# Rear_right_lamp_v3.net
KiCad netlist of a schematic drawn in EAGLE
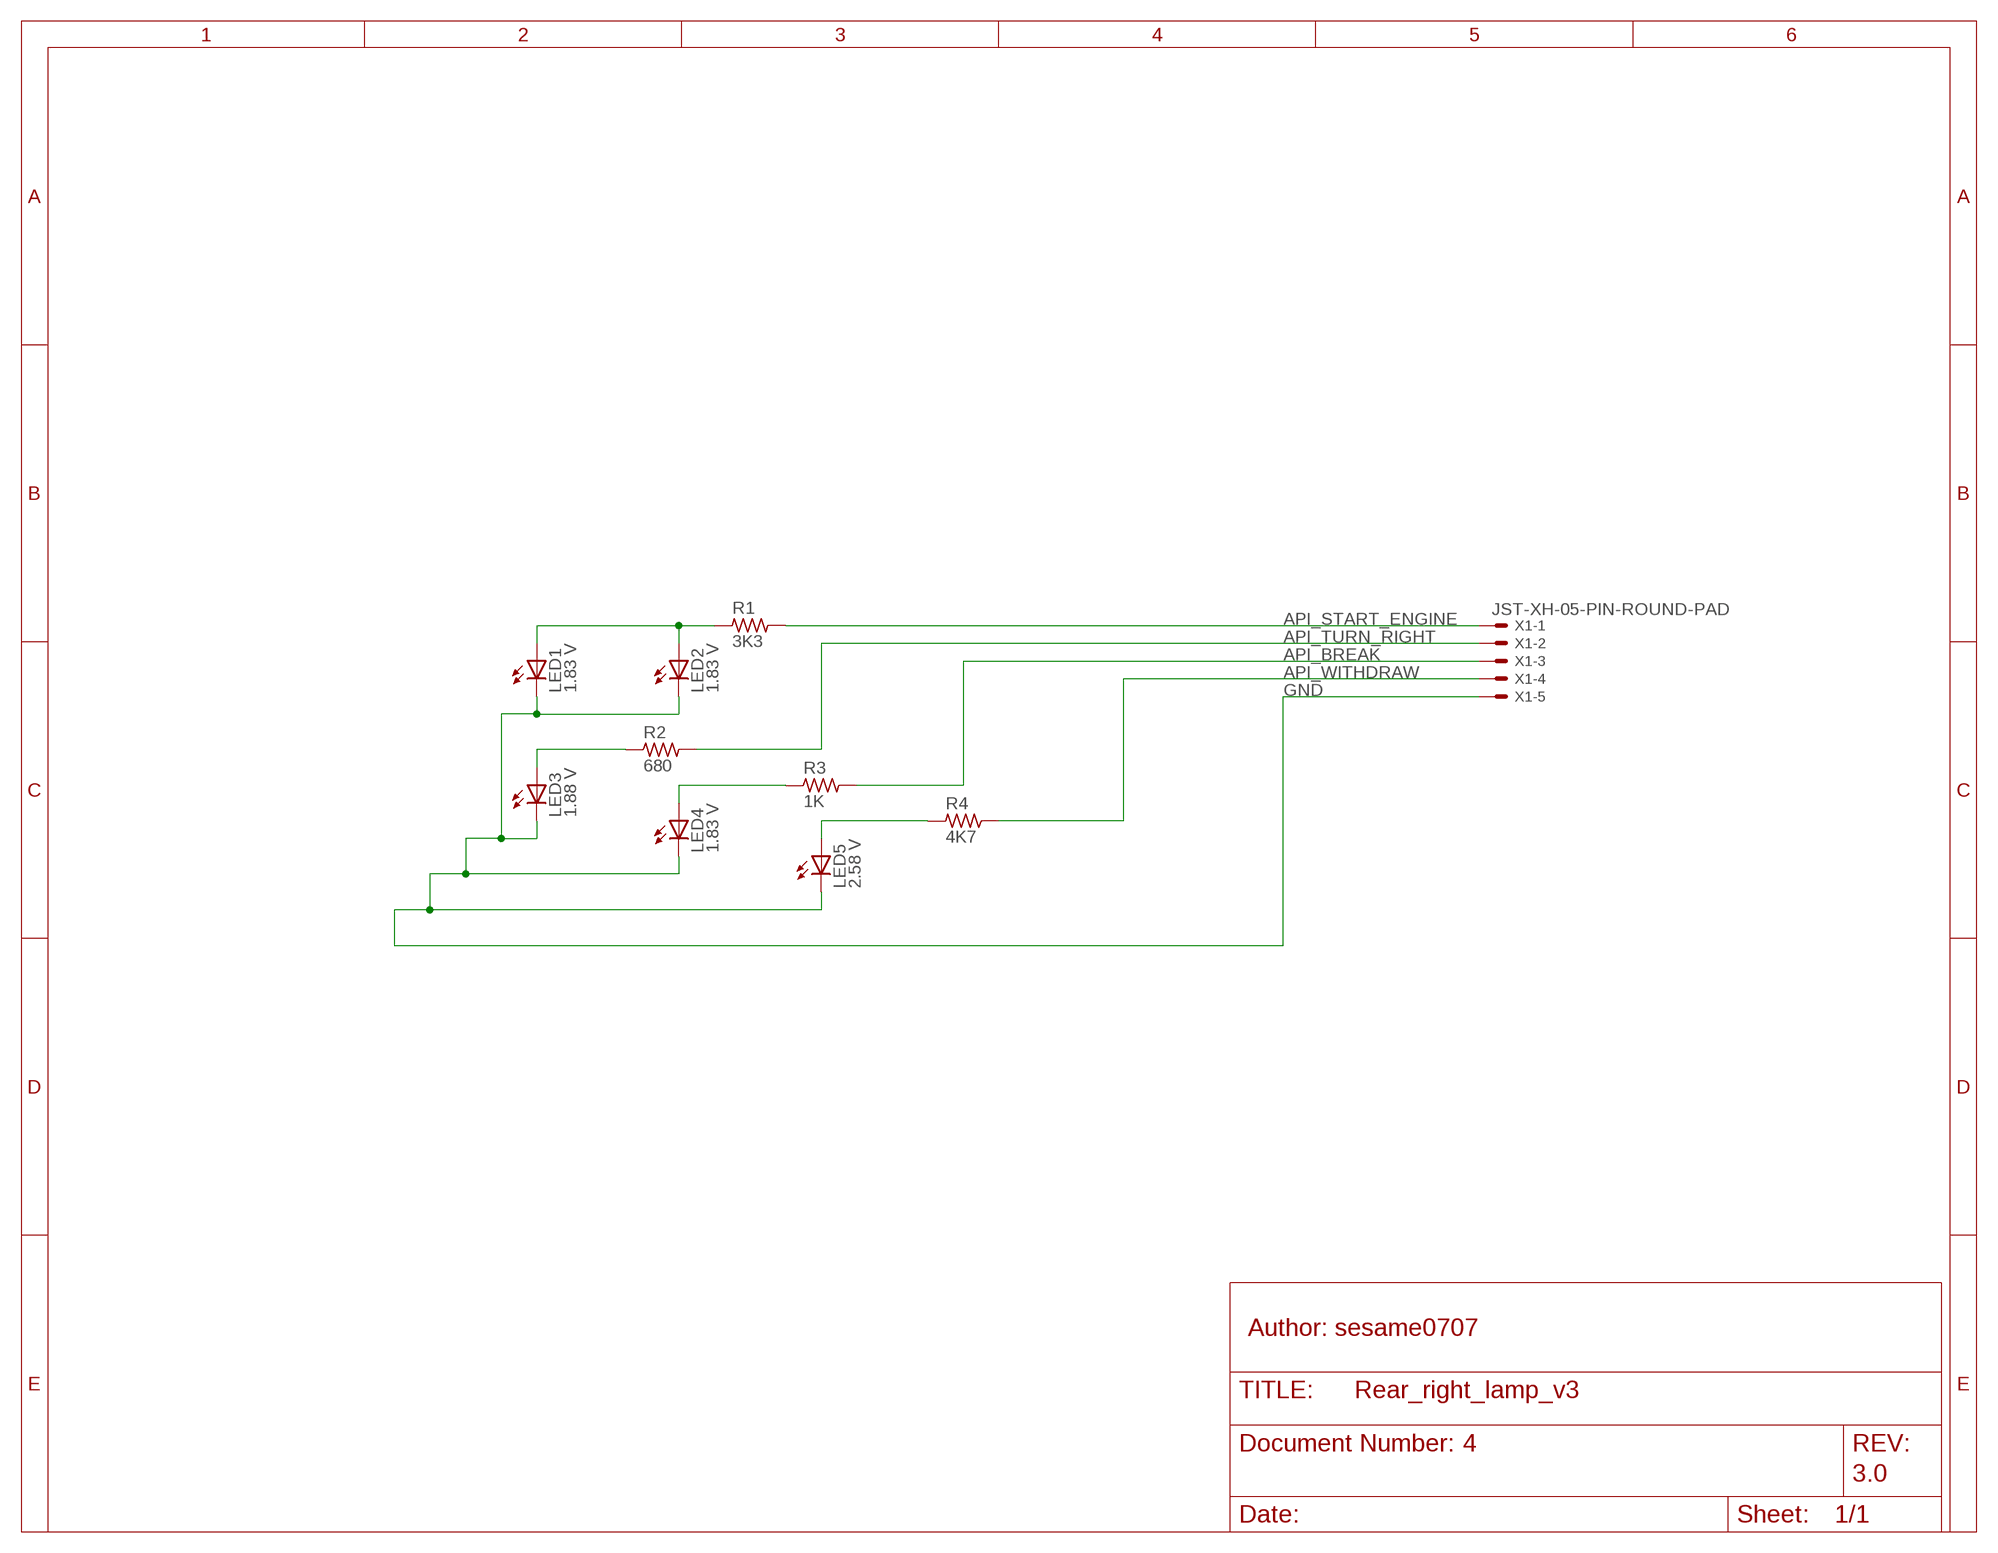
[diagram p0: schematic, sheet 1]

(export (version "E")
  (design (tool "Eeschema 10.0.6"))
  (components
    (comp (ref "LED1")
      (value "1.83 V")
      (footprint "eagle-import:LED5MM")
      (libsource (lib "eagle-import") (part "LED5MM"))
    )
    (comp (ref "LED2")
      (value "1.83 V")
      (footprint "eagle-import:LED5MM")
      (libsource (lib "eagle-import") (part "LED5MM"))
    )
    (comp (ref "LED3")
      (value "1.88 V")
      (footprint "eagle-import:LED5MM")
      (libsource (lib "eagle-import") (part "LED5MM"))
    )
    (comp (ref "LED4")
      (value "1.83 V")
      (footprint "eagle-import:LED5MM")
      (libsource (lib "eagle-import") (part "LED5MM"))
    )
    (comp (ref "LED5")
      (value "2.58 V")
      (footprint "eagle-import:LED5MM")
      (libsource (lib "eagle-import") (part "LED5MM"))
    )
    (comp (ref "R1")
      (value "3K3")
      (footprint "eagle-import:R1206")
      (libsource (lib "eagle-import") (part "R_1206"))
    )
    (comp (ref "R2")
      (value "680")
      (footprint "eagle-import:R1206")
      (libsource (lib "eagle-import") (part "R_1206"))
    )
    (comp (ref "R3")
      (value "1K")
      (footprint "eagle-import:R1206")
      (libsource (lib "eagle-import") (part "R_1206"))
    )
    (comp (ref "R4")
      (value "4K7")
      (footprint "eagle-import:R1206")
      (libsource (lib "eagle-import") (part "R_1206"))
    )
    (comp (ref "X1")
      (value "JST-XH-05-PIN-ROUND-PAD")
      (footprint "eagle-import:JST-XH-05-PACKAGE-ROUND-PAD")
      (libsource (lib "eagle-import") (part "JST-XH-05-PIN-ROUND-PAD"))
    )
  )
  (nets
    (net (code "1") (name "/API_BREAK") (class "Default")
      (node (ref "R3") (pin "2") (pinfunction "2_2") (pintype "passive"))
      (node (ref "X1") (pin "3") (pinfunction "S_3") (pintype "passive"))
    )
    (net (code "2") (name "/API_START_ENGINE") (class "Default")
      (node (ref "LED1") (pin "A") (pinfunction "A_A") (pintype "passive"))
      (node (ref "LED2") (pin "A") (pinfunction "A_A") (pintype "passive"))
      (node (ref "R1") (pin "1") (pinfunction "1_1") (pintype "passive"))
    )
    (net (code "3") (name "/API_TURN_RIGHT") (class "Default")
      (node (ref "R2") (pin "2") (pinfunction "2_2") (pintype "passive"))
      (node (ref "X1") (pin "2") (pinfunction "S_2") (pintype "passive"))
    )
    (net (code "4") (name "/API_WITHDRAW") (class "Default")
      (node (ref "R4") (pin "2") (pinfunction "2_2") (pintype "passive"))
      (node (ref "X1") (pin "4") (pinfunction "S_4") (pintype "passive"))
    )
    (net (code "5") (name "/GND") (class "Default")
      (node (ref "LED1") (pin "K") (pinfunction "C_K") (pintype "passive"))
      (node (ref "LED2") (pin "K") (pinfunction "C_K") (pintype "passive"))
      (node (ref "LED3") (pin "K") (pinfunction "C_K") (pintype "passive"))
      (node (ref "LED4") (pin "K") (pinfunction "C_K") (pintype "passive"))
      (node (ref "LED5") (pin "K") (pinfunction "C_K") (pintype "passive"))
      (node (ref "X1") (pin "5") (pinfunction "S_5") (pintype "passive"))
    )
    (net (code "6") (name "Net-(LED3-PadA)") (class "Default")
      (node (ref "LED3") (pin "A") (pinfunction "A_A") (pintype "passive"))
      (node (ref "R2") (pin "1") (pinfunction "1_1") (pintype "passive"))
    )
    (net (code "7") (name "Net-(LED4-PadA)") (class "Default")
      (node (ref "LED4") (pin "A") (pinfunction "A_A") (pintype "passive"))
      (node (ref "R3") (pin "1") (pinfunction "1_1") (pintype "passive"))
    )
    (net (code "8") (name "Net-(LED5-PadA)") (class "Default")
      (node (ref "LED5") (pin "A") (pinfunction "A_A") (pintype "passive"))
      (node (ref "R4") (pin "1") (pinfunction "1_1") (pintype "passive"))
    )
    (net (code "9") (name "Net-(X1A-S)") (class "Default")
      (node (ref "R1") (pin "2") (pinfunction "2_2") (pintype "passive"))
      (node (ref "X1") (pin "1") (pinfunction "S_1") (pintype "passive"))
    )
  )
)
